# LoRA_Schematic_v2.net
KiCad netlist of a schematic drawn in Altium Designer
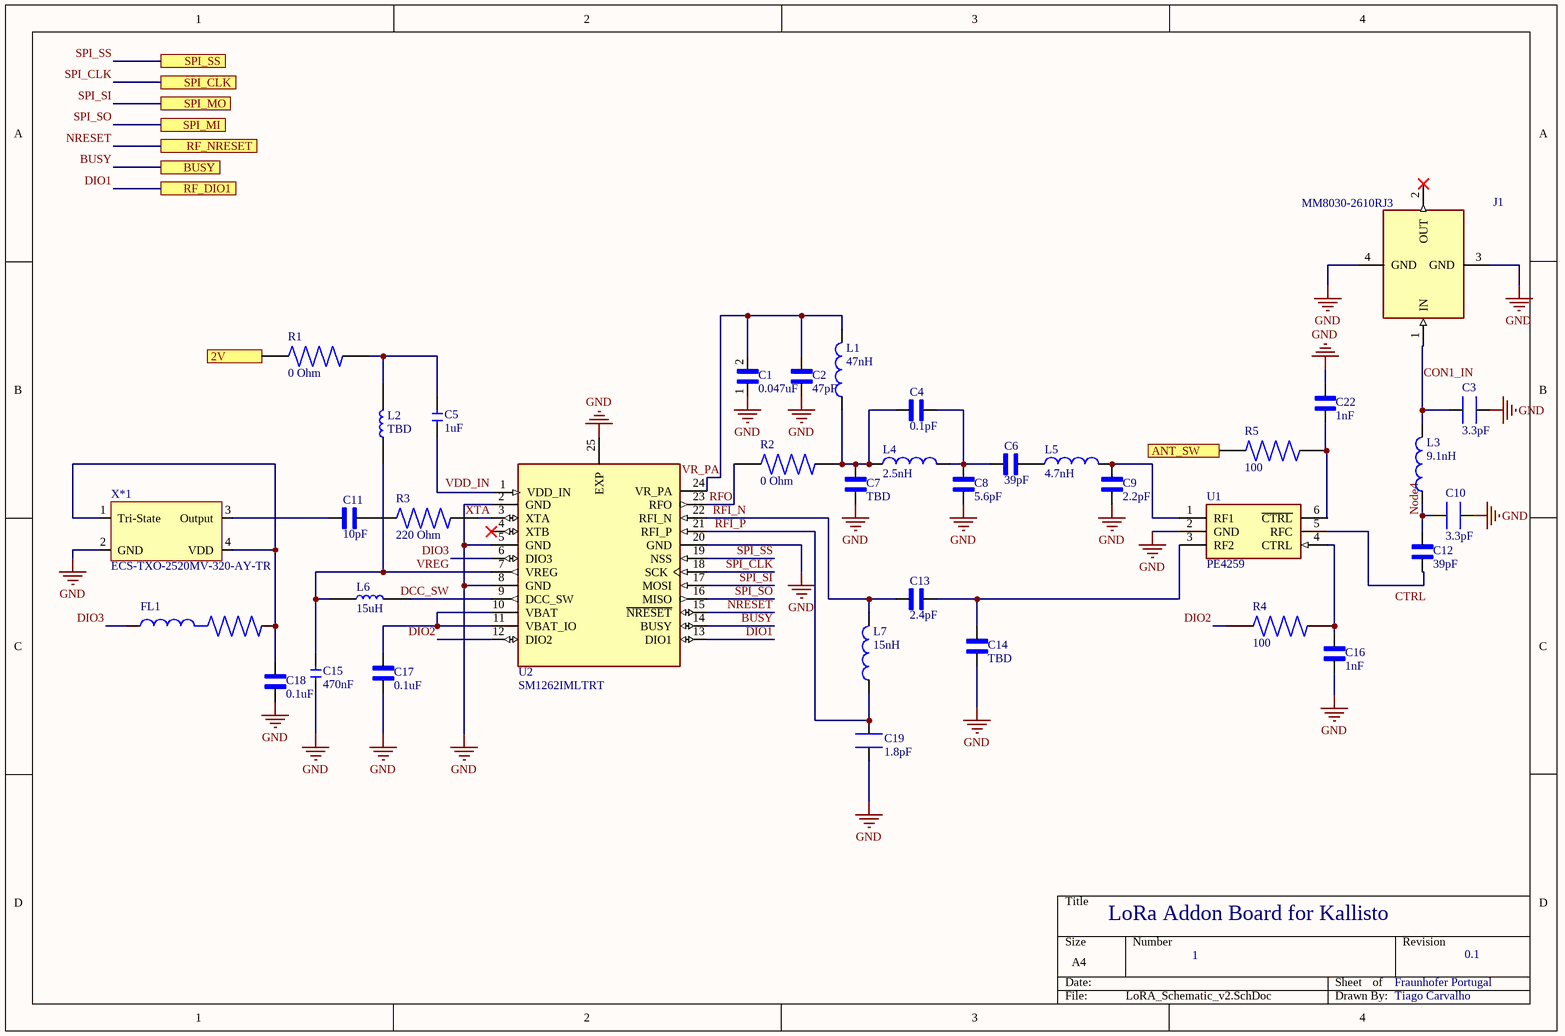
[diagram p0: LoRA_Schematic_v2.SchDoc]

(export (version "E")
  (design (tool "Eeschema 10.0.6"))
  (components
    (comp (ref "C1")
      (value "0.047uF")
      (footprint "CAPC1005X55N")
      (description "SMD Capacitor X7R(EIA) with Capacitance: 47000pF Tol. 10%. Rated Voltage: 16Vdc")
      (fields (field (name "MF") "muRata") (field (name "MP") "GRM155R71C473KA01J"))
      (libsource (lib "C_0.047uF") (part "GRM155R71C473KA01J"))
    )
    (comp (ref "C2")
      (value "47pF")
      (footprint "WCAP-CSGP_885012005059")
      (fields (field (name "MF") "wurth") (field (name "MP") "885012005059"))
      (libsource (lib "C_47pF") (part "885012005059"))
    )
    (comp (ref "C3")
      (value "3.3pF")
      (footprint "WCAP-CSRF_885392005011")
      (fields (field (name "MF") "Wurth") (field (name "MP") "885392005011"))
      (libsource (lib "C_3p3F") (part "885392005011"))
    )
    (comp (ref "C4")
      (value "0.1pF")
      (footprint "CAPC1005X55N")
      (description "0402 3.3 pF 50 V Â±0.1 pF Tolerance NP0 SMT Multilayer Ceramic Capacitor")
      (fields (field (name "MF") "Yageo") (field (name "MP") "CC0402BRNPO9BN3R3"))
      (libsource (lib "0.1pF") (part "CC0402BRNPO9BN3R3"))
    )
    (comp (ref "C5")
      (value "1uF")
      (footprint "C0402")
      (description "1ÂµF Â±10% 10V Ceramic Capacitor X5R 0402 _1005 Metric_")
      (fields (field (name "MP") "CC0402KRX5R6BB105") (field (name "MF") "Yageo"))
      (libsource (lib "C_1uF") (part "CERAMIC-1UF-10V-10%-X5R(0402)"))
    )
    (comp (ref "C6")
      (value "39pF")
      (footprint "CAPC1005X55N")
      (fields (field (name "MP") "C0402C390J5GAC"))
      (libsource (lib "") (part "C0402C390J5GAC_1"))
    )
    (comp (ref "C7")
      (value "TBD")
      (footprint "CAPC1005X55N")
      (fields (field (name "MF") "Vishay"))
      (libsource (lib "C_5p6F") (part "VJ0402A5R6CXAPW1BC"))
    )
    (comp (ref "C8")
      (value "5.6pF")
      (footprint "CAPC1005X55N")
      (description "Cap Ceramic 5.6pF 50V C0G 0.25pF SMD 0402 125Â°C Paper T/R")
      (fields (field (name "MP") "VJ0402A5R6CXAPW1BC") (field (name "MF") "Vishay"))
      (libsource (lib "C_5p6F") (part "VJ0402A5R6CXAPW1BC"))
    )
    (comp (ref "C9")
      (value "2.2pF")
      (footprint "CAPC1005X55N")
      (description "CAP CER 2.2PF 50V C0G/NPO 0402")
      (fields (field (name "MF") "YAGEO") (field (name "MP") "CC0402BRNPO9BN2R2"))
      (libsource (lib "C_2p2F") (part "CC0402BRNPO9BN2R2"))
    )
    (comp (ref "C10")
      (value "3.3pF")
      (footprint "WCAP-CSRF_885392005011")
      (fields (field (name "MF") "Wurth") (field (name "MP") "885392005011"))
      (libsource (lib "C_3p3F") (part "885392005011"))
    )
    (comp (ref "C11")
      (value "10pF")
      (footprint "WCAP-CSGP_885012005055")
      (fields (field (name "MP") "885012005055"))
      (libsource (lib "C_10pF") (part "885012005055"))
    )
    (comp (ref "C12")
      (value "39pF")
      (footprint "CAPC1005X55N")
      (fields (field (name "MP") "C0402C390J5GAC"))
      (libsource (lib "C_39pF") (part "C0402C390J5GAC"))
    )
    (comp (ref "C13")
      (value "2.4pF")
      (footprint "CAPC1005X55N")
      (description "2.4pF Â±0.1pF 50V Ceramic Capacitor C0G, NP0 0402 (1005 Metric)")
      (fields (field (name "MP") "CC0402BRNPO9BN2R4") (field (name "MF") "Yageo"))
      (libsource (lib "C_2p4F") (part "CC0402BRNPO9BN2R4"))
    )
    (comp (ref "C14")
      (value "TBD")
      (footprint "CAPC1005X55N")
      (fields (field (name "MF") "Vishay"))
      (libsource (lib "C_5p6F") (part "VJ0402A5R6CXAPW1BC"))
    )
    (comp (ref "C15")
      (value "470nF")
      (footprint "C0402")
      (description "0.47ÂµF Â±10% 10V Ceramic Capacitor X5R 0402 (1005 Metric)")
      (fields (field (name "MF") "Yageo") (field (name "MP") "CC0402KRX5R6BB474"))
      (libsource (lib "C_470nf") (part "CERAMIC-470NF-10V-10%-X5R(0402)"))
    )
    (comp (ref "C16")
      (value "1nF")
      (footprint "CAPC1005X56N")
      (fields (field (name "MF") "AVX") (field (name "MP") "0402ZD102KAT2A"))
      (libsource (lib "C_1nF") (part "0402ZD102KAT2A"))
    )
    (comp (ref "C17")
      (value "0.1uF")
      (footprint "WCAP-CSGP_885012205037")
      (fields
        (field (name "MF") "Wurth Electronics Inc")
        (field (name "MP") "885012205037")
        (field (name "BUYPART") "https://www.snapeda.com/parts/885012205037/Wurth%20Electronics%20Inc/view-part/4217417/?ref=eda")
      )
      (libsource (lib "C_0.1u") (part "885012205037"))
    )
    (comp (ref "C18")
      (value "0.1uF")
      (footprint "WCAP-CSGP_885012205037")
      (fields
        (field (name "MF") "Wurth Electronics Inc")
        (field (name "MP") "885012205037")
        (field (name "BUYPART") "https://www.snapeda.com/parts/885012205037/Wurth%20Electronics%20Inc/view-part/4217417/?ref=eda")
      )
      (libsource (lib "C_0.1u") (part "885012205037"))
    )
    (comp (ref "C19")
      (value "1.8pF")
      (footprint "WCAP-CSRF_885392005008")
      (fields (field (name "MP") "885392005008"))
      (libsource (lib "C_1p8F") (part "885392005008"))
    )
    (comp (ref "C22")
      (value "1nF")
      (footprint "CAPC1005X56N")
      (fields (field (name "MF") "AVX") (field (name "MP") "0402ZD102KAT2A"))
      (libsource (lib "C_1nF") (part "0402ZD102KAT2A"))
    )
    (comp (ref "FL1")
      (value "BLM15PG100SN1D")
      (footprint "BEADC1005X55N")
      (description "FERRITE, BEAD, 0402, 0.025OHM, 1A")
      (libsource (lib "FB1") (part "BLM15PG100SN1D"))
    )
    (comp (ref "J1")
      (value "MM8030-2610RJ3")
      (footprint "MURATA_MM8030-2610RJ3")
      (description "SWG Connector Receptacle, Female Socket 50Ohm Surface Mount Solder")
      (fields (field (name "MF") "Murata") (field (name "DIGI-KEY_PART_NUMBER") "490-5907-1-ND"))
      (libsource (lib "conector") (part "MM8030-2610RJ3"))
    )
    (comp (ref "L1")
      (value "47nH")
      (footprint "INDC1005X60N")
      (description "LQW15 Series 0402 47 nH Â±5 % 210 mA 1.08 Ohm SMT Unshielded Wirewound Inductor")
      (fields (field (name "MF") "Murata") (field (name "MP") "LQW15AN47NJ00D"))
      (libsource (lib "L_47nH") (part "LQW15AN47NJ00D"))
    )
    (comp (ref "L2")
      (value "TBD")
      (footprint "INDC2012X87N")
      (libsource (lib "") (part "MLZ2012M150WT000_1"))
    )
    (comp (ref "L3")
      (value "9.1nH")
      (footprint "INDC1006X60N")
      (description "Inductor with Inductance: 9.1nH Tol. +/-3%, Package: 0402 (1005)")
      (fields (field (name "MF") "Murata") (field (name "MP") "LQW15AN9N1H00D"))
      (libsource (lib "L_9n1H") (part "LQW15AN9N1H00D"))
    )
    (comp (ref "L4")
      (value "2.5nH")
      (footprint "INDC1006X60N")
      (description "Inductor with Inductance: 2.5nH Tol. +/-0.2nH, Package: 0402 _1005_")
      (fields (field (name "MP") "LQW15AN2N5C00D") (field (name "DIGI-KEY_PART_NUMBER") "490-6798-1-ND"))
      (libsource (lib "L_2n5H") (part "LQW15AN2N5C00D"))
    )
    (comp (ref "L5")
      (value "4.7nH")
      (footprint "INDC1006X60N")
      (fields (field (name "MF") "Murata") (field (name "MP") "LQW15AN4N7C00D"))
      (libsource (lib "L_4n7H") (part "LQW15AN4N7C00D"))
    )
    (comp (ref "L6")
      (value "15uH")
      (footprint "INDC2012X87N")
      (description "Surface Mount High Frequency Inductor, MLZ Series, 15 H, 20%, 0805 [2012 Metric], 22 MHz")
      (fields (field (name "MF") "TDK-Lambda") (field (name "MP") "MLZ2012M150WT000"))
      (libsource (lib "L_15uH") (part "MLZ2012M150WT000"))
    )
    (comp (ref "L7")
      (value "15nH")
      (footprint "INDC1006X60N")
      (description "Inductor with Inductance: 15nH Tol. +/-3%, Package: 0402 (1005)")
      (fields (field (name "MP") "LQW15AN15NH00D") (field (name "MF") "Murata"))
      (libsource (lib "L_15nH") (part "LQW15AN15NH00D"))
    )
    (comp (ref "R1")
      (value "0 Ohm")
      (footprint "RESC1005X35N")
      (description "0 Ohms Jumper 0.063W, 1/16W Chip Resistor 0402 (1005 Metric) Thick Film")
      (fields (field (name "MF") "Vishay Dale") (field (name "DIGI-KEY_PART_NUMBER") "541-4062-1-ND"))
      (libsource (lib "R_0") (part "CRCW04020000Z0EDC"))
    )
    (comp (ref "R2")
      (value "0 Ohm")
      (footprint "RESC1005X35N")
      (description "0 Ohms Jumper 0.063W, 1/16W Chip Resistor 0402 (1005 Metric) Thick Film")
      (fields (field (name "MF") "Vishay Dale") (field (name "DIGI-KEY_PART_NUMBER") "541-4062-1-ND"))
      (libsource (lib "R_0") (part "CRCW04020000Z0EDC"))
    )
    (comp (ref "R3")
      (value "220 Ohm")
      (footprint "RESC1005X40N")
      (description "Res Thick Film 0402 220 Ohm 5% 1/16W Â±200ppm/Â°C Molded SMD SMD Paper T/R")
      (fields (field (name "MP") "CRCW0402220RJNED"))
      (libsource (lib "R_220") (part "CRCW0402220RJNED"))
    )
    (comp (ref "R4")
      (value "100")
      (footprint "RESC1005X40N")
      (description "Res Thick Film 0402 100 Ohm 1% 1/16W Â±100ppm/Â°C Molded SMD SMD Paper T/R")
      (fields (field (name "MP") "CRCW0402100RFKTD"))
      (libsource (lib "R_100") (part "CRCW0402100RFKTD"))
    )
    (comp (ref "R5")
      (value "100")
      (footprint "RESC1005X40N")
      (description "Res Thick Film 0402 100 Ohm 1% 1/16W Â±100ppm/Â°C Molded SMD SMD Paper T/R")
      (fields (field (name "MP") "CRCW0402100RFKTD"))
      (libsource (lib "R_100") (part "CRCW0402100RFKTD"))
    )
    (comp (ref "U1")
      (value "PE4259")
      (footprint "PCBComponent_1")
      (description "UltraCMOSÂ® Switch, SPDT For Use With PE4259")
      (fields (field (name "MF") "pSemi"))
      (libsource (lib "PE4259_ours") (part "PE4259"))
    )
    (comp (ref "U2")
      (value "SM1262IMLTRT")
      (footprint "SX")
      (description "IC RF TxRx Only General ISM < 1GHz LoRaWAN 150MHz ~ 960MHz 24-VFQFN Exposed Pad")
      (fields (field (name "MP") "1262IMLTRT"))
      (libsource (lib "SX1262_ours") (part "SM1262"))
    )
    (comp (ref "X*1")
      (value "ECS-TXO-2520MV-320-AY-TR")
      (footprint "OSCDFN250X200X89-4N")
      (description "32MHz TCXO CMOS Oscillator 1.7V ~ 3.6V Enable/Disable 4-SMD, No Lead")
      (libsource (lib "ESC") (part "TXCO"))
    )
  )
  (nets
    (net (code "1") (name "/2V") (class "Default")
      (node (ref "R1") (pin "1") (pinfunction "1_1") (pintype "passive"))
    )
    (net (code "2") (name "/ANT_SW") (class "Default")
      (node (ref "R5") (pin "1") (pinfunction "1_1") (pintype "passive"))
    )
    (net (code "3") (name "/BUSY") (class "Default")
      (node (ref "U2") (pin "14") (pinfunction "BUSY_14") (pintype "bidirectional"))
    )
    (net (code "6") (name "/DCC_SW") (class "Default")
      (node (ref "L6") (pin "2") (pinfunction "2_2") (pintype "passive"))
      (node (ref "U2") (pin "9") (pinfunction "DCC_SW_9") (pintype "output"))
    )
    (net (code "7") (name "/DIO1") (class "Default")
      (node (ref "U2") (pin "13") (pinfunction "DIO1_13") (pintype "bidirectional"))
    )
    (net (code "8") (name "/DIO2") (class "Default")
      (node (ref "R4") (pin "1") (pinfunction "1_1") (pintype "passive"))
      (node (ref "U2") (pin "12") (pinfunction "DIO2_12") (pintype "bidirectional"))
    )
    (net (code "9") (name "/DIO3") (class "Default")
      (node (ref "FL1") (pin "1") (pinfunction "1_1") (pintype "passive"))
      (node (ref "U2") (pin "6") (pinfunction "DIO3_6") (pintype "bidirectional"))
    )
    (net (code "10") (name "/NRESET") (class "Default")
      (node (ref "U2") (pin "15") (pinfunction "~{NRESET}_15") (pintype "bidirectional"))
    )
    (net (code "11") (name "/Node4") (class "Default")
      (node (ref "C10") (pin "1") (pinfunction "1_1") (pintype "passive"))
      (node (ref "C12") (pin "1") (pinfunction "1_1") (pintype "passive"))
      (node (ref "L3") (pin "1") (pinfunction "1_1") (pintype "passive"))
    )
    (net (code "12") (name "/RFI_N") (class "Default")
      (node (ref "C13") (pin "2") (pinfunction "2_2") (pintype "passive"))
      (node (ref "L7") (pin "2") (pinfunction "2_2") (pintype "passive"))
      (node (ref "U2") (pin "22") (pinfunction "RFI_N_22") (pintype "input"))
    )
    (net (code "13") (name "/RFI_P") (class "Default")
      (node (ref "C19") (pin "2") (pinfunction "2_2") (pintype "passive"))
      (node (ref "L7") (pin "1") (pinfunction "1_1") (pintype "passive"))
      (node (ref "U2") (pin "21") (pinfunction "RFI_P_21") (pintype "input"))
    )
    (net (code "14") (name "/RFO") (class "Default")
      (node (ref "R2") (pin "1") (pinfunction "1_1") (pintype "passive"))
      (node (ref "U2") (pin "23") (pinfunction "RFO_23") (pintype "output"))
    )
    (net (code "15") (name "/SPI_CLK") (class "Default")
      (node (ref "U2") (pin "18") (pinfunction "SCK_18") (pintype "input"))
    )
    (net (code "16") (name "/SPI_SI") (class "Default")
      (node (ref "U2") (pin "17") (pinfunction "MOSI_17") (pintype "input"))
    )
    (net (code "17") (name "/SPI_SO") (class "Default")
      (node (ref "U2") (pin "16") (pinfunction "MISO_16") (pintype "output"))
    )
    (net (code "18") (name "/SPI_SS") (class "Default")
      (node (ref "U2") (pin "19") (pinfunction "NSS_19") (pintype "input"))
    )
    (net (code "20") (name "/VREG") (class "Default")
      (node (ref "C15") (pin "2") (pinfunction "2_2") (pintype "passive"))
      (node (ref "L2") (pin "1") (pinfunction "1_1") (pintype "passive"))
      (node (ref "L6") (pin "1") (pinfunction "1_1") (pintype "passive"))
      (node (ref "U2") (pin "7") (pinfunction "VREG_7") (pintype "output"))
    )
    (net (code "21") (name "/VR_PA") (class "Default")
      (node (ref "C1") (pin "2") (pinfunction "2_2") (pintype "passive"))
      (node (ref "C2") (pin "2") (pinfunction "2_2") (pintype "passive"))
      (node (ref "L1") (pin "2") (pinfunction "2_2") (pintype "passive"))
      (node (ref "U2") (pin "24") (pinfunction "VR_PA_24") (pintype "power_in"))
    )
    (net (code "22") (name "/XTA") (class "Default")
      (node (ref "R3") (pin "2") (pinfunction "2_2") (pintype "passive"))
      (node (ref "U2") (pin "3") (pinfunction "XTA_3") (pintype "bidirectional"))
    )
    (net (code "23") (name "GND") (class "Default")
      (node (ref "C1") (pin "1") (pinfunction "1_1") (pintype "passive"))
      (node (ref "C10") (pin "2") (pinfunction "2_2") (pintype "passive"))
      (node (ref "C14") (pin "1") (pinfunction "1_1") (pintype "passive"))
      (node (ref "C15") (pin "1") (pinfunction "1_1") (pintype "passive"))
      (node (ref "C16") (pin "1") (pinfunction "1_1") (pintype "passive"))
      (node (ref "C17") (pin "1") (pinfunction "1_1") (pintype "passive"))
      (node (ref "C18") (pin "1") (pinfunction "1_1") (pintype "passive"))
      (node (ref "C19") (pin "1") (pinfunction "1_1") (pintype "passive"))
      (node (ref "C2") (pin "1") (pinfunction "1_1") (pintype "passive"))
      (node (ref "C22") (pin "2") (pinfunction "2_2") (pintype "passive"))
      (node (ref "C3") (pin "2") (pinfunction "2_2") (pintype "passive"))
      (node (ref "C7") (pin "1") (pinfunction "1_1") (pintype "passive"))
      (node (ref "C8") (pin "1") (pinfunction "1_1") (pintype "passive"))
      (node (ref "C9") (pin "2") (pinfunction "2_2") (pintype "passive"))
      (node (ref "J1") (pin "3") (pinfunction "GND_3") (pintype "power_in"))
      (node (ref "J1") (pin "4") (pinfunction "GND_4") (pintype "power_in"))
      (node (ref "U1") (pin "2") (pinfunction "GND_2") (pintype "power_in"))
      (node (ref "U2") (pin "2") (pinfunction "GND_2") (pintype "power_in"))
      (node (ref "U2") (pin "20") (pinfunction "GND_20") (pintype "power_in"))
      (node (ref "U2") (pin "25") (pinfunction "EXP_25") (pintype "power_in"))
      (node (ref "U2") (pin "5") (pinfunction "GND_5") (pintype "power_in"))
      (node (ref "U2") (pin "8") (pinfunction "GND_8") (pintype "power_in"))
      (node (ref "X*1") (pin "2") (pinfunction "GND_2") (pintype "passive"))
    )
    (net (code "24") (name "Net-(C4-Pad1)") (class "Default")
      (node (ref "C4") (pin "1") (pinfunction "1_1") (pintype "passive"))
      (node (ref "C6") (pin "2") (pinfunction "2_2") (pintype "passive"))
      (node (ref "C8") (pin "2") (pinfunction "2_2") (pintype "passive"))
      (node (ref "L4") (pin "2") (pinfunction "2_2") (pintype "passive"))
    )
    (net (code "25") (name "Net-(C4-Pad2)") (class "Default")
      (node (ref "C4") (pin "2") (pinfunction "2_2") (pintype "passive"))
      (node (ref "C7") (pin "2") (pinfunction "2_2") (pintype "passive"))
      (node (ref "L1") (pin "1") (pinfunction "1_1") (pintype "passive"))
      (node (ref "L4") (pin "1") (pinfunction "1_1") (pintype "passive"))
      (node (ref "R2") (pin "2") (pinfunction "2_2") (pintype "passive"))
    )
    (net (code "26") (name "Net-(C5-Pad2)") (class "Default")
      (node (ref "C5") (pin "2") (pinfunction "2_2") (pintype "passive"))
      (node (ref "L2") (pin "2") (pinfunction "2_2") (pintype "passive"))
      (node (ref "R1") (pin "2") (pinfunction "2_2") (pintype "passive"))
    )
    (net (code "27") (name "Net-(C6-Pad1)") (class "Default")
      (node (ref "C6") (pin "1") (pinfunction "1_1") (pintype "passive"))
      (node (ref "L5") (pin "1") (pinfunction "1_1") (pintype "passive"))
    )
    (net (code "28") (name "Net-(C11-Pad1)") (class "Default")
      (node (ref "C11") (pin "1") (pinfunction "1_1") (pintype "passive"))
      (node (ref "R3") (pin "1") (pinfunction "1_1") (pintype "passive"))
    )
    (net (code "29") (name "Net-(J1-IN)") (class "Default")
      (node (ref "C3") (pin "1") (pinfunction "1_1") (pintype "passive"))
      (node (ref "J1") (pin "1") (pinfunction "IN_1") (pintype "input"))
      (node (ref "L3") (pin "2") (pinfunction "2_2") (pintype "passive"))
    )
    (net (code "30") (name "Net-(U1-CTRL)") (class "Default")
      (node (ref "C16") (pin "2") (pinfunction "2_2") (pintype "passive"))
      (node (ref "R4") (pin "2") (pinfunction "2_2") (pintype "passive"))
      (node (ref "U1") (pin "4") (pinfunction "CTRL_4") (pintype "input"))
    )
    (net (code "31") (name "Net-(U1-RF1)") (class "Default")
      (node (ref "C9") (pin "1") (pinfunction "1_1") (pintype "passive"))
      (node (ref "L5") (pin "2") (pinfunction "2_2") (pintype "passive"))
      (node (ref "U1") (pin "1") (pinfunction "RF1_1") (pintype "passive"))
    )
    (net (code "32") (name "Net-(U1-RF2)") (class "Default")
      (node (ref "C13") (pin "1") (pinfunction "1_1") (pintype "passive"))
      (node (ref "C14") (pin "2") (pinfunction "2_2") (pintype "passive"))
      (node (ref "U1") (pin "3") (pinfunction "RF2_3") (pintype "passive"))
    )
    (net (code "33") (name "Net-(U1-RFC)") (class "Default")
      (node (ref "C12") (pin "2") (pinfunction "2_2") (pintype "passive"))
      (node (ref "U1") (pin "5") (pinfunction "RFC_5") (pintype "passive"))
    )
    (net (code "34") (name "Net-(U1-~{CTRL})") (class "Default")
      (node (ref "C22") (pin "1") (pinfunction "1_1") (pintype "passive"))
      (node (ref "R5") (pin "2") (pinfunction "2_2") (pintype "passive"))
      (node (ref "U1") (pin "6") (pinfunction "~{CTRL}_6") (pintype "power_in"))
    )
    (net (code "35") (name "Net-(U2-VBAT)") (class "Default")
      (node (ref "C17") (pin "2") (pinfunction "2_2") (pintype "passive"))
      (node (ref "U2") (pin "10") (pinfunction "VBAT_10") (pintype "power_in"))
      (node (ref "U2") (pin "11") (pinfunction "VBAT_IO_11") (pintype "power_in"))
    )
    (net (code "36") (name "Net-(U2-VDD_IN)") (class "Default")
      (node (ref "C5") (pin "1") (pinfunction "1_1") (pintype "passive"))
      (node (ref "U2") (pin "1") (pinfunction "VDD_IN_1") (pintype "input"))
    )
    (net (code "37") (name "Net-(X*1-Output)") (class "Default")
      (node (ref "C11") (pin "2") (pinfunction "2_2") (pintype "passive"))
      (node (ref "X*1") (pin "3") (pinfunction "Output_3") (pintype "passive"))
    )
    (net (code "38") (name "Net-(X*1-Tri-State)") (class "Default")
      (node (ref "C18") (pin "2") (pinfunction "2_2") (pintype "passive"))
      (node (ref "FL1") (pin "2") (pinfunction "2_2") (pintype "passive"))
      (node (ref "X*1") (pin "1") (pinfunction "Tri-State_1") (pintype "passive"))
      (node (ref "X*1") (pin "4") (pinfunction "VDD_4") (pintype "passive"))
    )
    (net (code "39") (name "unconnected-(J1-OUT-Pad2)") (class "Default")
      (node (ref "J1") (pin "2") (pinfunction "OUT_2") (pintype "output+no_connect"))
    )
    (net (code "40") (name "unconnected-(U2-XTB-Pad4)") (class "Default")
      (node (ref "U2") (pin "4") (pinfunction "XTB_4") (pintype "bidirectional+no_connect"))
    )
  )
)
